# ScopeDefl.net
KiCad netlist of a schematic drawn in Altium Designer
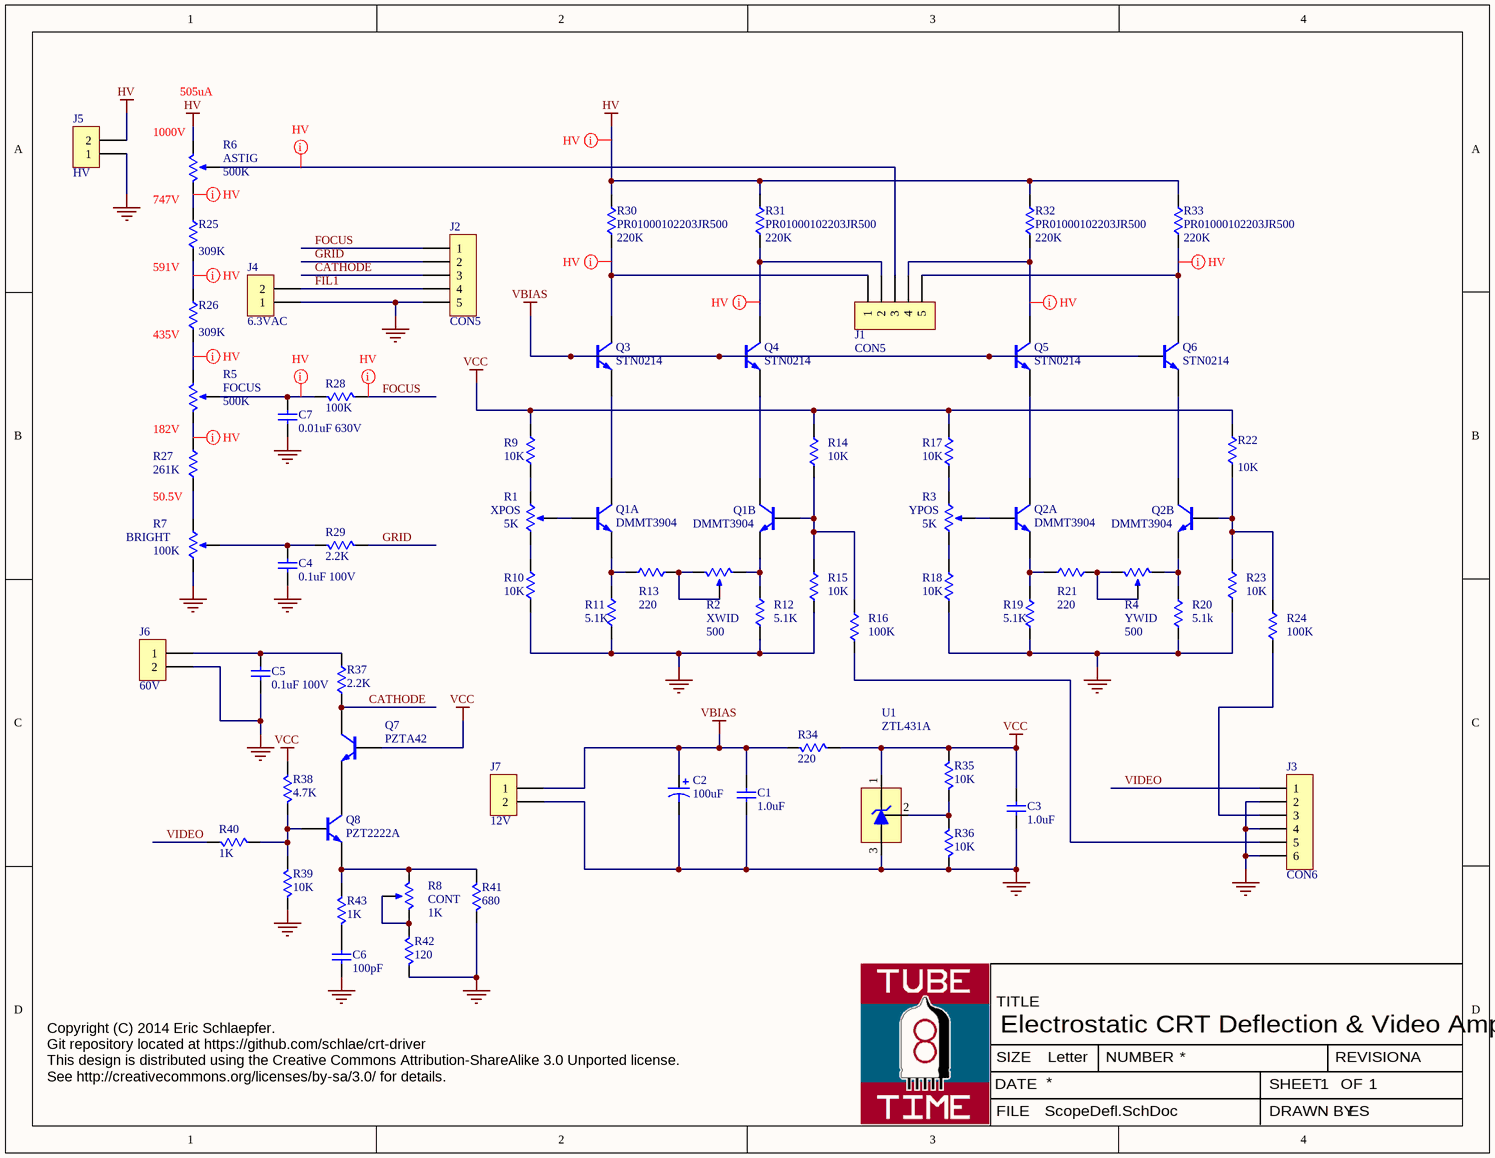
[diagram p0: ScopeDefl.SchDoc]

(export (version "E")
  (design (tool "Eeschema 10.0.6"))
  (components
    (comp (ref "C1")
      (value "1.0uF")
      (footprint "G_0805[2012]")
      (description "Capacitor")
      (fields (field (name "MANUFPART") "C2012X7R1E105K125AB") (field (name "Comment") "Cap"))
      (libsource (lib "ClikCommon") (part "Cap"))
    )
    (comp (ref "C2")
      (value "100uF")
      (footprint "CAP_R100x250")
      (description "Polarized Capacitor")
      (fields (field (name "MANUFPART") "UVR1E101MED1TD") (field (name "Comment") "Cap Pol2"))
      (libsource (lib "ClikCommon") (part "CapP"))
    )
    (comp (ref "C3")
      (value "1.0uF")
      (footprint "G_0805[2012]")
      (description "Capacitor")
      (fields (field (name "MANUFPART") "C2012X7R1E105K125AB") (field (name "Comment") "Cap"))
      (libsource (lib "ClikCommon") (part "Cap"))
    )
    (comp (ref "C4")
      (value "0.1uF 100V")
      (footprint "G_1206[3216]")
      (description "Capacitor")
      (fields (field (name "Comment") "Cap"))
      (libsource (lib "ClikCommon") (part "Cap"))
    )
    (comp (ref "C5")
      (value "0.1uF 100V")
      (footprint "G_1206[3216]")
      (description "Capacitor")
      (fields (field (name "Comment") "Cap"))
      (libsource (lib "ClikCommon") (part "Cap"))
    )
    (comp (ref "C6")
      (value "100pF")
      (footprint "G_0805[2012]")
      (description "Capacitor")
      (fields (field (name "Comment") "Cap"))
      (libsource (lib "ClikCommon") (part "Cap"))
    )
    (comp (ref "C7")
      (value "0.01uF 630V")
      (footprint "G_1206[3216]")
      (description "Capacitor")
      (fields (field (name "Comment") "Cap"))
      (libsource (lib "ClikCommon") (part "Cap"))
    )
    (comp (ref "J1")
      (value "CON5")
      (footprint "HDR5S156")
      (description "Connector, 5 pin")
      (libsource (lib "") (part "CON5_1"))
    )
    (comp (ref "J2")
      (value "CON5")
      (footprint "HDR5S156")
      (description "Connector, 5 pin")
      (libsource (lib "ClikConnectors") (part "CON5"))
    )
    (comp (ref "J3")
      (value "CON6")
      (footprint "HDR6S")
      (description "Connector, 5 pin")
      (libsource (lib "ClikConnectors") (part "CON6"))
    )
    (comp (ref "J4")
      (value "6.3VAC")
      (footprint "HDR2S156")
      (description "Connector, 2 pin")
      (libsource (lib "") (part "CON2_1"))
    )
    (comp (ref "J5")
      (value "HV")
      (footprint "HDR3S156M1")
      (description "Connector, 2 pin")
      (libsource (lib "") (part "CON2_1"))
    )
    (comp (ref "J6")
      (value "60V")
      (footprint "HDR2S")
      (description "Connector, 2 pin")
      (libsource (lib "ClikConnectors") (part "CON2"))
    )
    (comp (ref "J7")
      (value "12V")
      (footprint "HDR2S")
      (description "Connector, 2 pin")
      (libsource (lib "ClikConnectors") (part "CON2"))
    )
    (comp (ref "Q1")
      (value "DMMT3904")
      (footprint "G_SC70")
      (description "NPN Dual Bipolar Transistor")
      (fields (field (name "MANUFPART") "DMMT3904W-7-F"))
      (libsource (lib "ClikCommon") (part "NPN_DUAL2"))
    )
    (comp (ref "Q2")
      (value "DMMT3904")
      (footprint "G_SC70")
      (description "NPN Dual Bipolar Transistor")
      (fields (field (name "MANUFPART") "DMMT3904W-7-F"))
      (libsource (lib "ClikCommon") (part "NPN_DUAL2"))
    )
    (comp (ref "Q3")
      (value "STN0214")
      (footprint "G_SOT223TNC")
      (description "NPN Bipolar Transistor")
      (fields (field (name "MANUFPART") "511-STN0214"))
      (libsource (lib "ClikCommon") (part "NPN"))
    )
    (comp (ref "Q4")
      (value "STN0214")
      (footprint "G_SOT223TNC")
      (description "NPN Bipolar Transistor")
      (fields (field (name "MANUFPART") "511-STN0214"))
      (libsource (lib "ClikCommon") (part "NPN"))
    )
    (comp (ref "Q5")
      (value "STN0214")
      (footprint "G_SOT223TNC")
      (description "NPN Bipolar Transistor")
      (fields (field (name "MANUFPART") "511-STN0214"))
      (libsource (lib "ClikCommon") (part "NPN"))
    )
    (comp (ref "Q6")
      (value "STN0214")
      (footprint "G_SOT223TNC")
      (description "NPN Bipolar Transistor")
      (fields (field (name "MANUFPART") "511-STN0214"))
      (libsource (lib "ClikCommon") (part "NPN"))
    )
    (comp (ref "Q7")
      (value "PZTA42")
      (footprint "G_SOT223T")
      (description "NPN Bipolar Transistor")
      (fields (field (name "Comment") "NPN"))
      (libsource (lib "") (part "NPN_1"))
    )
    (comp (ref "Q8")
      (value "PZT2222A")
      (footprint "G_SOT223T")
      (description "NPN Bipolar Transistor")
      (fields (field (name "Comment") "NPN"))
      (libsource (lib "ClikCommon") (part "NPN"))
    )
    (comp (ref "R1")
      (value "XPOS")
      (footprint "POT_TRIM BOURNS 3386F")
      (description "Variable Resistor")
      (fields (field (name "ALTIUM_VALUE") "5K") (field (name "MANUFPART") "3386F-1-502LF"))
      (libsource (lib "ClikCommon") (part "Pot"))
    )
    (comp (ref "R2")
      (value "XWID")
      (footprint "POT_TRIM BOURNS 3386F")
      (description "Variable Resistor")
      (fields (field (name "ALTIUM_VALUE") "500") (field (name "MANUFPART") "3386F-1-501LF"))
      (libsource (lib "ClikCommon") (part "Pot"))
    )
    (comp (ref "R3")
      (value "YPOS")
      (footprint "POT_TRIM BOURNS 3386F")
      (description "Variable Resistor")
      (fields (field (name "ALTIUM_VALUE") "5K") (field (name "MANUFPART") "3386F-1-502LF"))
      (libsource (lib "ClikCommon") (part "Pot"))
    )
    (comp (ref "R4")
      (value "YWID")
      (footprint "POT_TRIM BOURNS 3386F")
      (description "Variable Resistor")
      (fields (field (name "ALTIUM_VALUE") "500") (field (name "MANUFPART") "3386F-1-501LF"))
      (libsource (lib "ClikCommon") (part "Pot"))
    )
    (comp (ref "R5")
      (value "FOCUS")
      (footprint "POT_TRIM BOURNS 3386F")
      (description "Variable Resistor")
      (fields (field (name "ALTIUM_VALUE") "500K") (field (name "MANUFPART") "3386F-1-504LF"))
      (libsource (lib "ClikCommon") (part "Pot"))
    )
    (comp (ref "R6")
      (value "ASTIG")
      (footprint "POT_TRIM BOURNS 3386F")
      (description "Variable Resistor")
      (fields (field (name "ALTIUM_VALUE") "500K") (field (name "MANUFPART") "3386F-1-504LF"))
      (libsource (lib "ClikCommon") (part "Pot"))
    )
    (comp (ref "R7")
      (value "BRIGHT")
      (footprint "POT_TRIM BOURNS 3386F")
      (description "Variable Resistor")
      (fields (field (name "ALTIUM_VALUE") "100K") (field (name "MANUFPART") "3386F-1-104LF"))
      (libsource (lib "ClikCommon") (part "Pot"))
    )
    (comp (ref "R8")
      (value "CONT")
      (footprint "POT_TRIM BOURNS 3386F")
      (description "Variable Resistor")
      (fields (field (name "ALTIUM_VALUE") "1K") (field (name "MANUFPART") "3386F-1-102LF"))
      (libsource (lib "ClikCommon") (part "Pot"))
    )
    (comp (ref "R9")
      (value "10K")
      (footprint "G_0805[2012]")
      (description "Resistor")
      (fields (field (name "MANUFPART") "CRCW080510K0FKEB") (field (name "Comment") "Res1"))
      (libsource (lib "ClikCommon") (part "Res"))
    )
    (comp (ref "R10")
      (value "10K")
      (footprint "G_0805[2012]")
      (description "Resistor")
      (fields (field (name "MANUFPART") "CRCW080510K0FKEB") (field (name "Comment") "Res1"))
      (libsource (lib "ClikCommon") (part "Res"))
    )
    (comp (ref "R11")
      (value "5.1K")
      (footprint "G_0805[2012]")
      (description "Resistor")
      (fields (field (name "MANUFPART") "CRCW08055K10FKEA") (field (name "Comment") "Res1"))
      (libsource (lib "ClikCommon") (part "Res"))
    )
    (comp (ref "R12")
      (value "5.1K")
      (footprint "G_0805[2012]")
      (description "Resistor")
      (fields (field (name "MANUFPART") "CRCW08055K10FKEA") (field (name "Comment") "Res1"))
      (libsource (lib "ClikCommon") (part "Res"))
    )
    (comp (ref "R13")
      (value "220")
      (footprint "G_0805[2012]")
      (description "Resistor")
      (fields (field (name "MANUFPART") "CRCW0805220RFKEA") (field (name "Comment") "Res1"))
      (libsource (lib "ClikCommon") (part "Res"))
    )
    (comp (ref "R14")
      (value "10K")
      (footprint "G_0805[2012]")
      (description "Resistor")
      (fields (field (name "MANUFPART") "CRCW080510K0FKEB") (field (name "Comment") "Res1"))
      (libsource (lib "ClikCommon") (part "Res"))
    )
    (comp (ref "R15")
      (value "10K")
      (footprint "G_0805[2012]")
      (description "Resistor")
      (fields (field (name "MANUFPART") "CRCW080510K0FKEB") (field (name "Comment") "Res1"))
      (libsource (lib "ClikCommon") (part "Res"))
    )
    (comp (ref "R16")
      (value "100K")
      (footprint "G_0805[2012]")
      (description "Resistor")
      (fields (field (name "MANUFPART") "CRCW0805100KFKEA") (field (name "Comment") "Res1"))
      (libsource (lib "ClikCommon") (part "Res"))
    )
    (comp (ref "R17")
      (value "10K")
      (footprint "G_0805[2012]")
      (description "Resistor")
      (fields (field (name "MANUFPART") "CRCW080510K0FKEB") (field (name "Comment") "Res1"))
      (libsource (lib "ClikCommon") (part "Res"))
    )
    (comp (ref "R18")
      (value "10K")
      (footprint "G_0805[2012]")
      (description "Resistor")
      (fields (field (name "MANUFPART") "CRCW080510K0FKEB") (field (name "Comment") "Res1"))
      (libsource (lib "ClikCommon") (part "Res"))
    )
    (comp (ref "R19")
      (value "5.1K")
      (footprint "G_0805[2012]")
      (description "Resistor")
      (fields (field (name "MANUFPART") "CRCW08055K10FKEA") (field (name "Comment") "Res1"))
      (libsource (lib "ClikCommon") (part "Res"))
    )
    (comp (ref "R20")
      (value "5.1k")
      (footprint "G_0805[2012]")
      (description "Resistor")
      (fields (field (name "MANUFPART") "CRCW08055K10FKEA") (field (name "Comment") "Res1"))
      (libsource (lib "ClikCommon") (part "Res"))
    )
    (comp (ref "R21")
      (value "220")
      (footprint "G_0805[2012]")
      (description "Resistor")
      (fields (field (name "MANUFPART") "CRCW0805220RFKEA") (field (name "Comment") "Res1"))
      (libsource (lib "ClikCommon") (part "Res"))
    )
    (comp (ref "R22")
      (value "10K")
      (footprint "G_0805[2012]")
      (description "Resistor")
      (fields (field (name "MANUFPART") "CRCW080510K0FKEB") (field (name "Comment") "Res1"))
      (libsource (lib "ClikCommon") (part "Res"))
    )
    (comp (ref "R23")
      (value "10K")
      (footprint "G_0805[2012]")
      (description "Resistor")
      (fields (field (name "MANUFPART") "CRCW080510K0FKEB") (field (name "Comment") "Res1"))
      (libsource (lib "ClikCommon") (part "Res"))
    )
    (comp (ref "R24")
      (value "100K")
      (footprint "G_0805[2012]")
      (description "Resistor")
      (fields (field (name "MANUFPART") "CRCW0805100KFKEA") (field (name "Comment") "Res1"))
      (libsource (lib "ClikCommon") (part "Res"))
    )
    (comp (ref "R25")
      (value "309K")
      (footprint "G_1206[3216]")
      (description "Resistor")
      (fields (field (name "MANUFPART") "ERJ-8ENF3093V") (field (name "Comment") "Res1"))
      (libsource (lib "ClikCommon") (part "Res"))
    )
    (comp (ref "R26")
      (value "309K")
      (footprint "G_1206[3216]")
      (description "Resistor")
      (fields (field (name "MANUFPART") "ERJ-8ENF3093V") (field (name "Comment") "Res1"))
      (libsource (lib "ClikCommon") (part "Res"))
    )
    (comp (ref "R27")
      (value "261K")
      (footprint "G_1206[3216]")
      (description "Resistor")
      (fields (field (name "MANUFPART") "CRCW1206261KFKEA") (field (name "Comment") "Res1"))
      (libsource (lib "ClikCommon") (part "Res"))
    )
    (comp (ref "R28")
      (value "100K")
      (footprint "G_0805[2012]")
      (description "Resistor")
      (fields (field (name "MANUFPART") "CRCW0805100KFKEA") (field (name "Comment") "Res1"))
      (libsource (lib "ClikCommon") (part "Res"))
    )
    (comp (ref "R29")
      (value "2.2K")
      (footprint "G_0805[2012]")
      (description "Resistor")
      (fields (field (name "MANUFPART") "ERJ-6ENF2201V") (field (name "Comment") "Res1"))
      (libsource (lib "ClikCommon") (part "Res"))
    )
    (comp (ref "R30")
      (value "PR01000102203JR500")
      (footprint "RES450X100")
      (description "Resistor")
      (fields (field (name "ALTIUM_VALUE") "220K"))
      (libsource (lib "ClikCommon") (part "Res"))
    )
    (comp (ref "R31")
      (value "PR01000102203JR500")
      (footprint "RES450X100")
      (description "Resistor")
      (fields (field (name "ALTIUM_VALUE") "220K"))
      (libsource (lib "ClikCommon") (part "Res"))
    )
    (comp (ref "R32")
      (value "PR01000102203JR500")
      (footprint "RES450X100")
      (description "Resistor")
      (fields (field (name "ALTIUM_VALUE") "220K"))
      (libsource (lib "ClikCommon") (part "Res"))
    )
    (comp (ref "R33")
      (value "PR01000102203JR500")
      (footprint "RES450X100")
      (description "Resistor")
      (fields (field (name "ALTIUM_VALUE") "220K"))
      (libsource (lib "ClikCommon") (part "Res"))
    )
    (comp (ref "R34")
      (value "220")
      (footprint "G_0805[2012]")
      (description "Resistor")
      (fields (field (name "MANUFPART") "CRCW0805220RFKEA") (field (name "Comment") "Res1"))
      (libsource (lib "ClikCommon") (part "Res"))
    )
    (comp (ref "R35")
      (value "10K")
      (footprint "G_0805[2012]")
      (description "Resistor")
      (fields (field (name "MANUFPART") "CRCW080510K0FKEB") (field (name "Comment") "Res1"))
      (libsource (lib "ClikCommon") (part "Res"))
    )
    (comp (ref "R36")
      (value "10K")
      (footprint "G_0805[2012]")
      (description "Resistor")
      (fields (field (name "MANUFPART") "CRCW080510K0FKEB") (field (name "Comment") "Res1"))
      (libsource (lib "ClikCommon") (part "Res"))
    )
    (comp (ref "R37")
      (value "2.2K")
      (footprint "G_1206[3216]")
      (description "Resistor")
      (fields (field (name "MANUFPART") "CRCW12062K20FKEA") (field (name "Comment") "Res1"))
      (libsource (lib "ClikCommon") (part "Res"))
    )
    (comp (ref "R38")
      (value "4.7K")
      (footprint "G_0805[2012]")
      (description "Resistor")
      (fields (field (name "MANUFPART") "CRCW08054K70FKEA") (field (name "Comment") "Res1"))
      (libsource (lib "ClikCommon") (part "Res"))
    )
    (comp (ref "R39")
      (value "10K")
      (footprint "G_0805[2012]")
      (description "Resistor")
      (fields (field (name "MANUFPART") "CRCW080510K0FKEB") (field (name "Comment") "Res1"))
      (libsource (lib "ClikCommon") (part "Res"))
    )
    (comp (ref "R40")
      (value "1K")
      (footprint "G_0805[2012]")
      (description "Resistor")
      (fields (field (name "MANUFPART") "CRCW08051K00JNEA") (field (name "Comment") "Res1"))
      (libsource (lib "ClikCommon") (part "Res"))
    )
    (comp (ref "R41")
      (value "680")
      (footprint "G_0805[2012]")
      (description "Resistor")
      (fields (field (name "MANUFPART") "CRCW0805680RFKEA") (field (name "Comment") "Res1"))
      (libsource (lib "ClikCommon") (part "Res"))
    )
    (comp (ref "R42")
      (value "120")
      (footprint "G_0805[2012]")
      (description "Resistor")
      (fields (field (name "MANUFPART") "CRCW0805120RFKEA") (field (name "Comment") "Res1"))
      (libsource (lib "ClikCommon") (part "Res"))
    )
    (comp (ref "R43")
      (value "1K")
      (footprint "G_0805[2012]")
      (description "Resistor")
      (fields (field (name "MANUFPART") "CRCW08051K00JNEA") (field (name "Comment") "Res1"))
      (libsource (lib "ClikCommon") (part "Res"))
    )
    (comp (ref "U1")
      (value "ZTL431A")
      (footprint "G_SOT23")
      (description "Adjustable Shunt Reg")
      (fields (field (name "MANUFPART") "ZTL431AFFTA"))
      (libsource (lib "ClikIC") (part "TL431"))
    )
  )
  (nets
    (net (code "1") (name "/CATHODE") (class "Default")
      (node (ref "J2") (pin "3") (pinfunction "3_3") (pintype "passive"))
      (node (ref "Q7") (pin "C") (pinfunction "C_C") (pintype "passive"))
      (node (ref "R37") (pin "1") (pinfunction "1_1") (pintype "passive"))
    )
    (net (code "2") (name "/FIL1") (class "Default")
      (node (ref "J2") (pin "4") (pinfunction "4_4") (pintype "passive"))
      (node (ref "J4") (pin "2") (pinfunction "2_2") (pintype "passive"))
    )
    (net (code "3") (name "/FOCUS") (class "Default")
      (node (ref "J2") (pin "1") (pinfunction "1_1") (pintype "passive"))
      (node (ref "R28") (pin "1") (pinfunction "1_1") (pintype "passive"))
    )
    (net (code "4") (name "/GRID") (class "Default")
      (node (ref "J2") (pin "2") (pinfunction "2_2") (pintype "passive"))
      (node (ref "R29") (pin "1") (pinfunction "1_1") (pintype "passive"))
    )
    (net (code "5") (name "/VIDEO") (class "Default")
      (node (ref "J3") (pin "1") (pinfunction "1_1") (pintype "passive"))
      (node (ref "R40") (pin "1") (pinfunction "1_1") (pintype "passive"))
    )
    (net (code "6") (name "GND") (class "Default")
      (node (ref "C1") (pin "1") (pinfunction "1_1") (pintype "passive"))
      (node (ref "C2") (pin "2") (pinfunction "2_2") (pintype "passive"))
      (node (ref "C3") (pin "1") (pinfunction "1_1") (pintype "passive"))
      (node (ref "C4") (pin "2") (pinfunction "2_2") (pintype "passive"))
      (node (ref "C5") (pin "2") (pinfunction "2_2") (pintype "passive"))
      (node (ref "C6") (pin "2") (pinfunction "2_2") (pintype "passive"))
      (node (ref "C7") (pin "2") (pinfunction "2_2") (pintype "passive"))
      (node (ref "J2") (pin "5") (pinfunction "5_5") (pintype "passive"))
      (node (ref "J3") (pin "2") (pinfunction "2_2") (pintype "passive"))
      (node (ref "J3") (pin "4") (pinfunction "4_4") (pintype "passive"))
      (node (ref "J3") (pin "6") (pinfunction "6_6") (pintype "passive"))
      (node (ref "J4") (pin "1") (pinfunction "1_1") (pintype "passive"))
      (node (ref "J5") (pin "1") (pinfunction "1_1") (pintype "passive"))
      (node (ref "J6") (pin "2") (pinfunction "2_2") (pintype "passive"))
      (node (ref "J7") (pin "2") (pinfunction "2_2") (pintype "passive"))
      (node (ref "R10") (pin "1") (pinfunction "1_1") (pintype "passive"))
      (node (ref "R11") (pin "1") (pinfunction "1_1") (pintype "passive"))
      (node (ref "R12") (pin "1") (pinfunction "1_1") (pintype "passive"))
      (node (ref "R15") (pin "2") (pinfunction "2_2") (pintype "passive"))
      (node (ref "R18") (pin "2") (pinfunction "2_2") (pintype "passive"))
      (node (ref "R19") (pin "2") (pinfunction "2_2") (pintype "passive"))
      (node (ref "R20") (pin "2") (pinfunction "2_2") (pintype "passive"))
      (node (ref "R23") (pin "1") (pinfunction "1_1") (pintype "passive"))
      (node (ref "R36") (pin "2") (pinfunction "2_2") (pintype "passive"))
      (node (ref "R39") (pin "2") (pinfunction "2_2") (pintype "passive"))
      (node (ref "R41") (pin "2") (pinfunction "2_2") (pintype "passive"))
      (node (ref "R42") (pin "2") (pinfunction "2_2") (pintype "passive"))
      (node (ref "R7") (pin "1") (pinfunction "TOP_1") (pintype "passive"))
      (node (ref "U1") (pin "3") (pinfunction "A_3") (pintype "passive"))
    )
    (net (code "7") (name "HV") (class "Default")
      (node (ref "J5") (pin "2") (pinfunction "2_2") (pintype "passive"))
      (node (ref "R30") (pin "2") (pinfunction "2_2") (pintype "passive"))
      (node (ref "R31") (pin "2") (pinfunction "2_2") (pintype "passive"))
      (node (ref "R32") (pin "2") (pinfunction "2_2") (pintype "passive"))
      (node (ref "R33") (pin "2") (pinfunction "2_2") (pintype "passive"))
      (node (ref "R6") (pin "1") (pinfunction "TOP_1") (pintype "passive"))
    )
    (net (code "8") (name "Net-(C5-Pad1)") (class "Default")
      (node (ref "C5") (pin "1") (pinfunction "1_1") (pintype "passive"))
      (node (ref "J6") (pin "1") (pinfunction "1_1") (pintype "passive"))
      (node (ref "R37") (pin "2") (pinfunction "2_2") (pintype "passive"))
    )
    (net (code "9") (name "Net-(C6-Pad1)") (class "Default")
      (node (ref "C6") (pin "1") (pinfunction "1_1") (pintype "passive"))
      (node (ref "R43") (pin "2") (pinfunction "2_2") (pintype "passive"))
    )
    (net (code "10") (name "Net-(J1-Pad1)") (class "Default")
      (node (ref "J1") (pin "1") (pinfunction "1_1") (pintype "passive"))
      (node (ref "Q3") (pin "C") (pinfunction "C_C") (pintype "passive"))
      (node (ref "R30") (pin "1") (pinfunction "1_1") (pintype "passive"))
    )
    (net (code "11") (name "Net-(J1-Pad2)") (class "Default")
      (node (ref "J1") (pin "2") (pinfunction "2_2") (pintype "passive"))
      (node (ref "Q4") (pin "C") (pinfunction "C_C") (pintype "passive"))
      (node (ref "R31") (pin "1") (pinfunction "1_1") (pintype "passive"))
    )
    (net (code "12") (name "Net-(J1-Pad4)") (class "Default")
      (node (ref "J1") (pin "4") (pinfunction "4_4") (pintype "passive"))
      (node (ref "Q5") (pin "C") (pinfunction "C_C") (pintype "passive"))
      (node (ref "R32") (pin "1") (pinfunction "1_1") (pintype "passive"))
    )
    (net (code "13") (name "Net-(J1-Pad5)") (class "Default")
      (node (ref "J1") (pin "5") (pinfunction "5_5") (pintype "passive"))
      (node (ref "Q6") (pin "C") (pinfunction "C_C") (pintype "passive"))
      (node (ref "R33") (pin "1") (pinfunction "1_1") (pintype "passive"))
    )
    (net (code "14") (name "Net-(J3-Pad3)") (class "Default")
      (node (ref "J3") (pin "3") (pinfunction "3_3") (pintype "passive"))
      (node (ref "R24") (pin "1") (pinfunction "1_1") (pintype "passive"))
    )
    (net (code "15") (name "Net-(J3-Pad5)") (class "Default")
      (node (ref "J3") (pin "5") (pinfunction "5_5") (pintype "passive"))
      (node (ref "R16") (pin "2") (pinfunction "2_2") (pintype "passive"))
    )
    (net (code "16") (name "Net-(Q1A-B1)") (class "Default")
      (node (ref "Q1") (pin "2") (pinfunction "B1_2") (pintype "passive"))
      (node (ref "R1") (pin "3") (pinfunction "TAP_3") (pintype "passive"))
    )
    (net (code "17") (name "Net-(Q1A-C1)") (class "Default")
      (node (ref "Q1") (pin "3") (pinfunction "C1_3") (pintype "passive"))
      (node (ref "Q3") (pin "E") (pinfunction "E_E") (pintype "passive"))
    )
    (net (code "18") (name "Net-(Q1A-E1)") (class "Default")
      (node (ref "Q1") (pin "4") (pinfunction "E1_4") (pintype "passive"))
      (node (ref "R11") (pin "2") (pinfunction "2_2") (pintype "passive"))
      (node (ref "R13") (pin "2") (pinfunction "2_2") (pintype "passive"))
    )
    (net (code "19") (name "Net-(Q1B-B2)") (class "Default")
      (node (ref "Q1") (pin "1") (pinfunction "B2_1") (pintype "passive"))
      (node (ref "R14") (pin "2") (pinfunction "2_2") (pintype "passive"))
      (node (ref "R15") (pin "1") (pinfunction "1_1") (pintype "passive"))
      (node (ref "R16") (pin "1") (pinfunction "1_1") (pintype "passive"))
    )
    (net (code "20") (name "Net-(Q1B-C2)") (class "Default")
      (node (ref "Q1") (pin "6") (pinfunction "C2_6") (pintype "passive"))
      (node (ref "Q4") (pin "E") (pinfunction "E_E") (pintype "passive"))
    )
    (net (code "21") (name "Net-(Q1B-E2)") (class "Default")
      (node (ref "Q1") (pin "5") (pinfunction "E2_5") (pintype "passive"))
      (node (ref "R12") (pin "2") (pinfunction "2_2") (pintype "passive"))
      (node (ref "R2") (pin "1") (pinfunction "TOP_1") (pintype "passive"))
    )
    (net (code "22") (name "Net-(Q2A-B1)") (class "Default")
      (node (ref "Q2") (pin "2") (pinfunction "B1_2") (pintype "passive"))
      (node (ref "R3") (pin "3") (pinfunction "TAP_3") (pintype "passive"))
    )
    (net (code "23") (name "Net-(Q2A-C1)") (class "Default")
      (node (ref "Q2") (pin "3") (pinfunction "C1_3") (pintype "passive"))
      (node (ref "Q5") (pin "E") (pinfunction "E_E") (pintype "passive"))
    )
    (net (code "24") (name "Net-(Q2A-E1)") (class "Default")
      (node (ref "Q2") (pin "4") (pinfunction "E1_4") (pintype "passive"))
      (node (ref "R19") (pin "1") (pinfunction "1_1") (pintype "passive"))
      (node (ref "R21") (pin "1") (pinfunction "1_1") (pintype "passive"))
    )
    (net (code "25") (name "Net-(Q2B-B2)") (class "Default")
      (node (ref "Q2") (pin "1") (pinfunction "B2_1") (pintype "passive"))
      (node (ref "R22") (pin "1") (pinfunction "1_1") (pintype "passive"))
      (node (ref "R23") (pin "2") (pinfunction "2_2") (pintype "passive"))
      (node (ref "R24") (pin "2") (pinfunction "2_2") (pintype "passive"))
    )
    (net (code "26") (name "Net-(Q2B-C2)") (class "Default")
      (node (ref "Q2") (pin "6") (pinfunction "C2_6") (pintype "passive"))
      (node (ref "Q6") (pin "E") (pinfunction "E_E") (pintype "passive"))
    )
    (net (code "27") (name "Net-(Q2B-E2)") (class "Default")
      (node (ref "Q2") (pin "5") (pinfunction "E2_5") (pintype "passive"))
      (node (ref "R20") (pin "1") (pinfunction "1_1") (pintype "passive"))
      (node (ref "R4") (pin "1") (pinfunction "TOP_1") (pintype "passive"))
    )
    (net (code "28") (name "Net-(Q7-PadE)") (class "Default")
      (node (ref "Q7") (pin "E") (pinfunction "E_E") (pintype "passive"))
      (node (ref "Q8") (pin "C") (pinfunction "C_C") (pintype "passive"))
    )
    (net (code "29") (name "Net-(Q8-PadB)") (class "Default")
      (node (ref "Q8") (pin "B") (pinfunction "B_B") (pintype "passive"))
      (node (ref "R38") (pin "2") (pinfunction "2_2") (pintype "passive"))
      (node (ref "R39") (pin "1") (pinfunction "1_1") (pintype "passive"))
      (node (ref "R40") (pin "2") (pinfunction "2_2") (pintype "passive"))
    )
    (net (code "30") (name "Net-(R1-BOT)") (class "Default")
      (node (ref "R1") (pin "2") (pinfunction "BOT_2") (pintype "passive"))
      (node (ref "R9") (pin "1") (pinfunction "1_1") (pintype "passive"))
    )
    (net (code "31") (name "Net-(R1-TOP)") (class "Default")
      (node (ref "R1") (pin "1") (pinfunction "TOP_1") (pintype "passive"))
      (node (ref "R10") (pin "2") (pinfunction "2_2") (pintype "passive"))
    )
    (net (code "32") (name "Net-(R2-BOT)") (class "Default")
      (node (ref "R13") (pin "1") (pinfunction "1_1") (pintype "passive"))
      (node (ref "R2") (pin "2") (pinfunction "BOT_2") (pintype "passive"))
      (node (ref "R2") (pin "3") (pinfunction "TAP_3") (pintype "passive"))
    )
    (net (code "33") (name "Net-(R3-BOT)") (class "Default")
      (node (ref "R17") (pin "2") (pinfunction "2_2") (pintype "passive"))
      (node (ref "R3") (pin "2") (pinfunction "BOT_2") (pintype "passive"))
    )
    (net (code "34") (name "Net-(R3-TOP)") (class "Default")
      (node (ref "R18") (pin "1") (pinfunction "1_1") (pintype "passive"))
      (node (ref "R3") (pin "1") (pinfunction "TOP_1") (pintype "passive"))
    )
    (net (code "35") (name "Net-(R4-BOT)") (class "Default")
      (node (ref "R21") (pin "2") (pinfunction "2_2") (pintype "passive"))
      (node (ref "R4") (pin "2") (pinfunction "BOT_2") (pintype "passive"))
      (node (ref "R4") (pin "3") (pinfunction "TAP_3") (pintype "passive"))
    )
    (net (code "36") (name "Net-(R5-BOT)") (class "Default")
      (node (ref "R27") (pin "2") (pinfunction "2_2") (pintype "passive"))
      (node (ref "R5") (pin "2") (pinfunction "BOT_2") (pintype "passive"))
    )
    (net (code "37") (name "Net-(R5-TAP)") (class "Default")
      (node (ref "C7") (pin "1") (pinfunction "1_1") (pintype "passive"))
      (node (ref "R28") (pin "2") (pinfunction "2_2") (pintype "passive"))
      (node (ref "R5") (pin "3") (pinfunction "TAP_3") (pintype "passive"))
    )
    (net (code "38") (name "Net-(R5-TOP)") (class "Default")
      (node (ref "R26") (pin "1") (pinfunction "1_1") (pintype "passive"))
      (node (ref "R5") (pin "1") (pinfunction "TOP_1") (pintype "passive"))
    )
    (net (code "39") (name "Net-(R6-BOT)") (class "Default")
      (node (ref "R25") (pin "2") (pinfunction "2_2") (pintype "passive"))
      (node (ref "R6") (pin "2") (pinfunction "BOT_2") (pintype "passive"))
    )
    (net (code "40") (name "Net-(R6-TAP)") (class "Default")
      (node (ref "J1") (pin "3") (pinfunction "3_3") (pintype "passive"))
      (node (ref "R6") (pin "3") (pinfunction "TAP_3") (pintype "passive"))
    )
    (net (code "41") (name "Net-(R7-BOT)") (class "Default")
      (node (ref "R27") (pin "1") (pinfunction "1_1") (pintype "passive"))
      (node (ref "R7") (pin "2") (pinfunction "BOT_2") (pintype "passive"))
    )
    (net (code "42") (name "Net-(R7-TAP)") (class "Default")
      (node (ref "C4") (pin "1") (pinfunction "1_1") (pintype "passive"))
      (node (ref "R29") (pin "2") (pinfunction "2_2") (pintype "passive"))
      (node (ref "R7") (pin "3") (pinfunction "TAP_3") (pintype "passive"))
    )
    (net (code "43") (name "Net-(R8-BOT)") (class "Default")
      (node (ref "Q8") (pin "E") (pinfunction "E_E") (pintype "passive"))
      (node (ref "R41") (pin "1") (pinfunction "1_1") (pintype "passive"))
      (node (ref "R43") (pin "1") (pinfunction "1_1") (pintype "passive"))
      (node (ref "R8") (pin "2") (pinfunction "BOT_2") (pintype "passive"))
    )
    (net (code "44") (name "Net-(R8-TAP)") (class "Default")
      (node (ref "R42") (pin "1") (pinfunction "1_1") (pintype "passive"))
      (node (ref "R8") (pin "1") (pinfunction "TOP_1") (pintype "passive"))
      (node (ref "R8") (pin "3") (pinfunction "TAP_3") (pintype "passive"))
    )
    (net (code "45") (name "Net-(R25-Pad1)") (class "Default")
      (node (ref "R25") (pin "1") (pinfunction "1_1") (pintype "passive"))
      (node (ref "R26") (pin "2") (pinfunction "2_2") (pintype "passive"))
    )
    (net (code "46") (name "Net-(U1-REF)") (class "Default")
      (node (ref "R35") (pin "2") (pinfunction "2_2") (pintype "passive"))
      (node (ref "R36") (pin "1") (pinfunction "1_1") (pintype "passive"))
      (node (ref "U1") (pin "2") (pinfunction "REF_2") (pintype "passive"))
    )
    (net (code "47") (name "VBIAS") (class "Default")
      (node (ref "C1") (pin "2") (pinfunction "2_2") (pintype "passive"))
      (node (ref "C2") (pin "1") (pinfunction "1_1") (pintype "passive"))
      (node (ref "J7") (pin "1") (pinfunction "1_1") (pintype "passive"))
      (node (ref "Q3") (pin "B") (pinfunction "B_B") (pintype "passive"))
      (node (ref "Q4") (pin "B") (pinfunction "B_B") (pintype "passive"))
      (node (ref "Q5") (pin "B") (pinfunction "B_B") (pintype "passive"))
      (node (ref "Q6") (pin "B") (pinfunction "B_B") (pintype "passive"))
      (node (ref "R34") (pin "2") (pinfunction "2_2") (pintype "passive"))
    )
    (net (code "48") (name "VCC") (class "Default")
      (node (ref "C3") (pin "2") (pinfunction "2_2") (pintype "passive"))
      (node (ref "Q7") (pin "B") (pinfunction "B_B") (pintype "passive"))
      (node (ref "R14") (pin "1") (pinfunction "1_1") (pintype "passive"))
      (node (ref "R17") (pin "1") (pinfunction "1_1") (pintype "passive"))
      (node (ref "R22") (pin "2") (pinfunction "2_2") (pintype "passive"))
      (node (ref "R34") (pin "1") (pinfunction "1_1") (pintype "passive"))
      (node (ref "R35") (pin "1") (pinfunction "1_1") (pintype "passive"))
      (node (ref "R38") (pin "1") (pinfunction "1_1") (pintype "passive"))
      (node (ref "R9") (pin "2") (pinfunction "2_2") (pintype "passive"))
      (node (ref "U1") (pin "1") (pinfunction "C_1") (pintype "passive"))
    )
  )
)
